# POWER_SUPPLY.net
KiCad netlist of a schematic drawn in Altium Designer
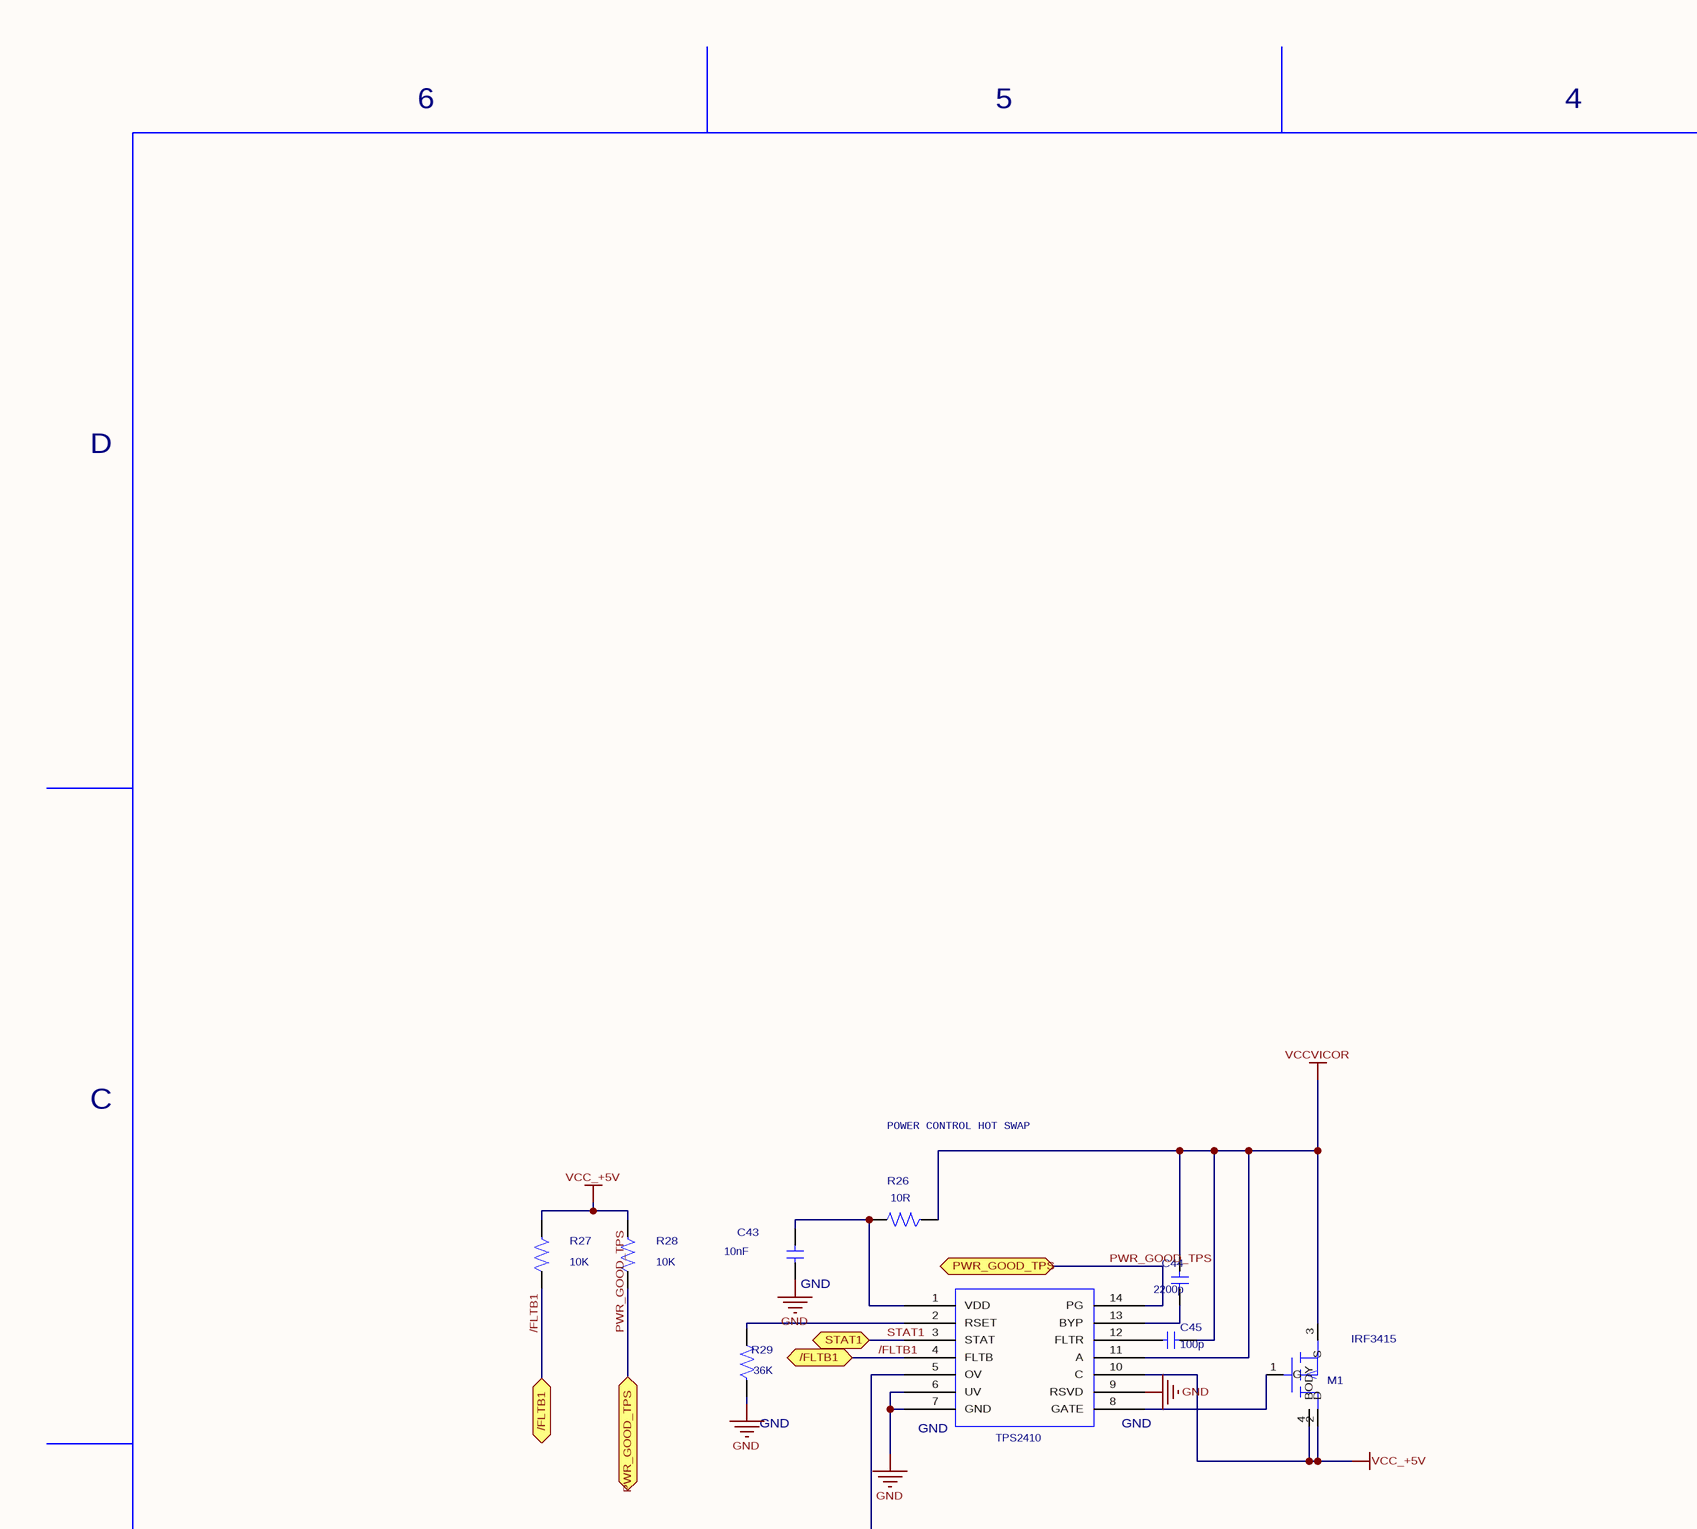
[diagram p0: POWER_SUPPLY.SchDoc, top left]
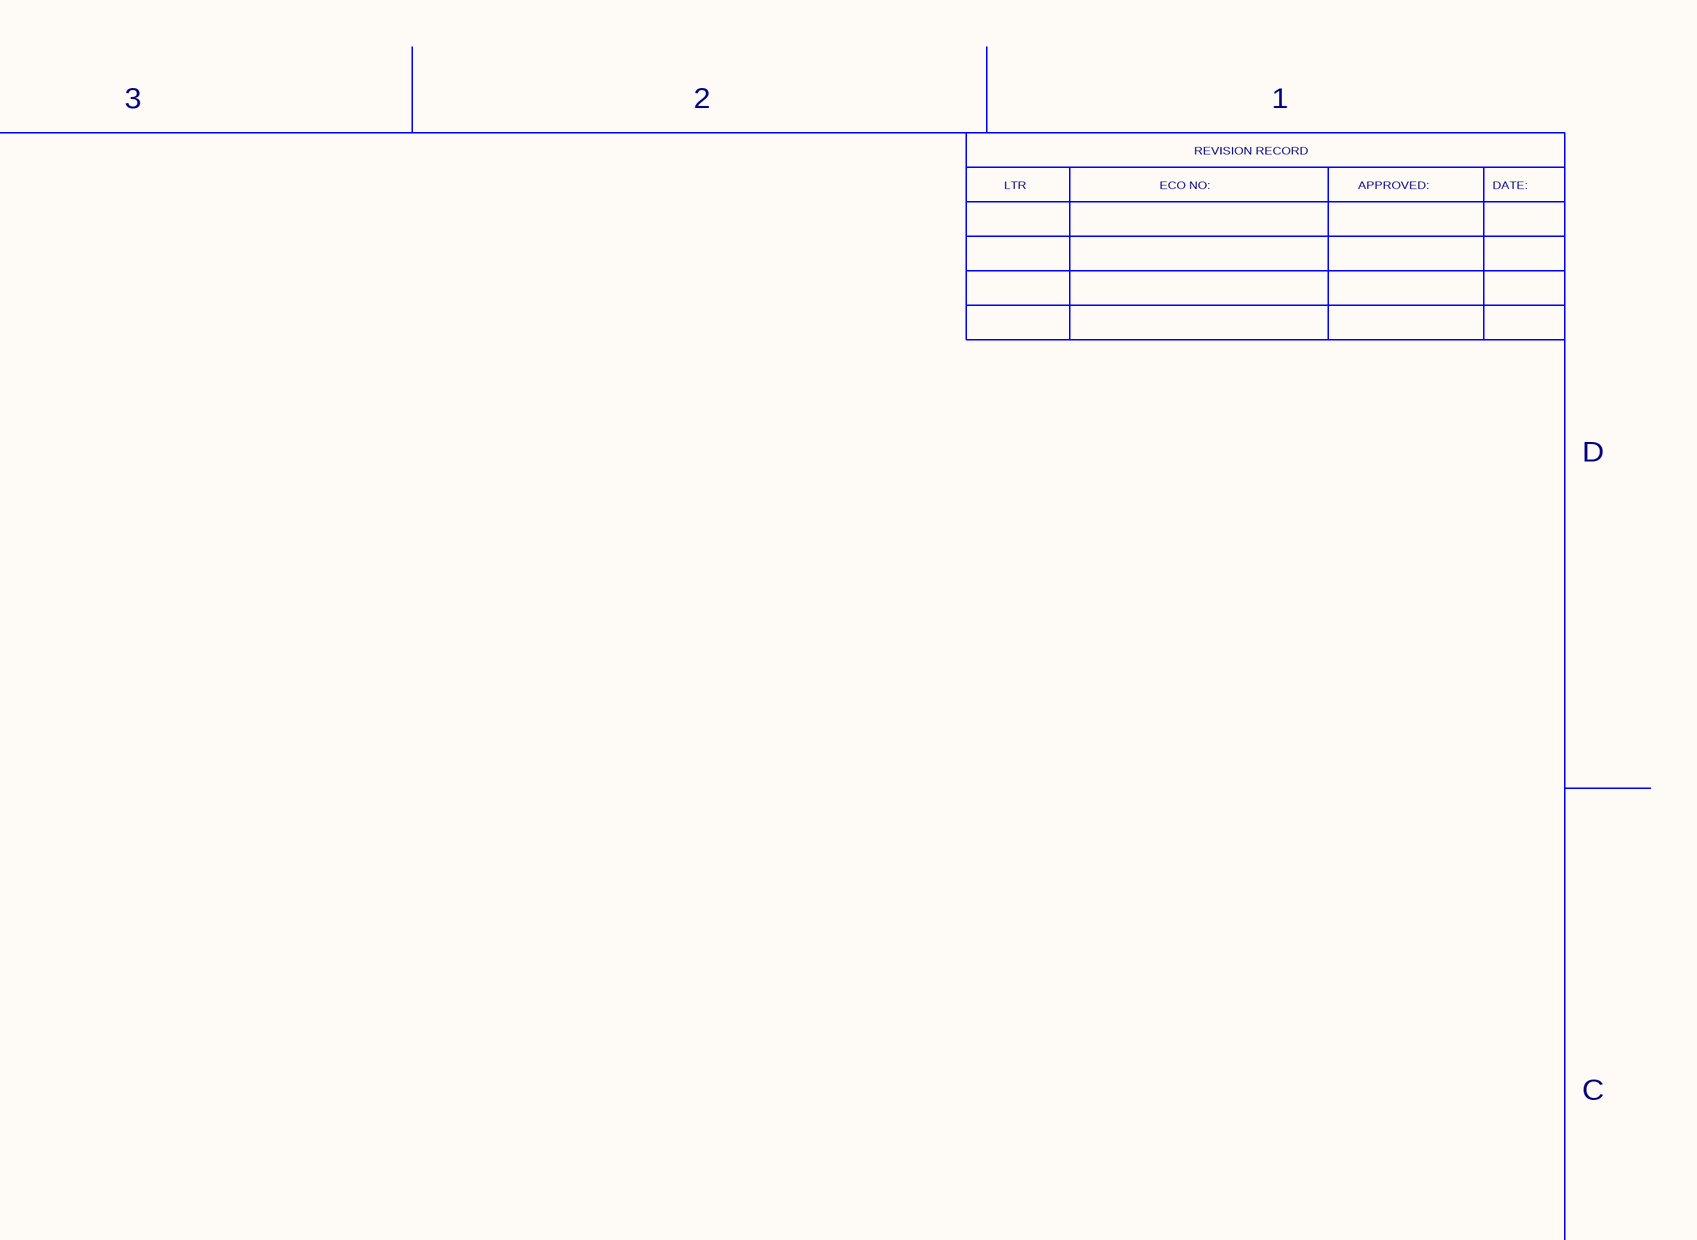
[diagram p1: POWER_SUPPLY.SchDoc, top right]
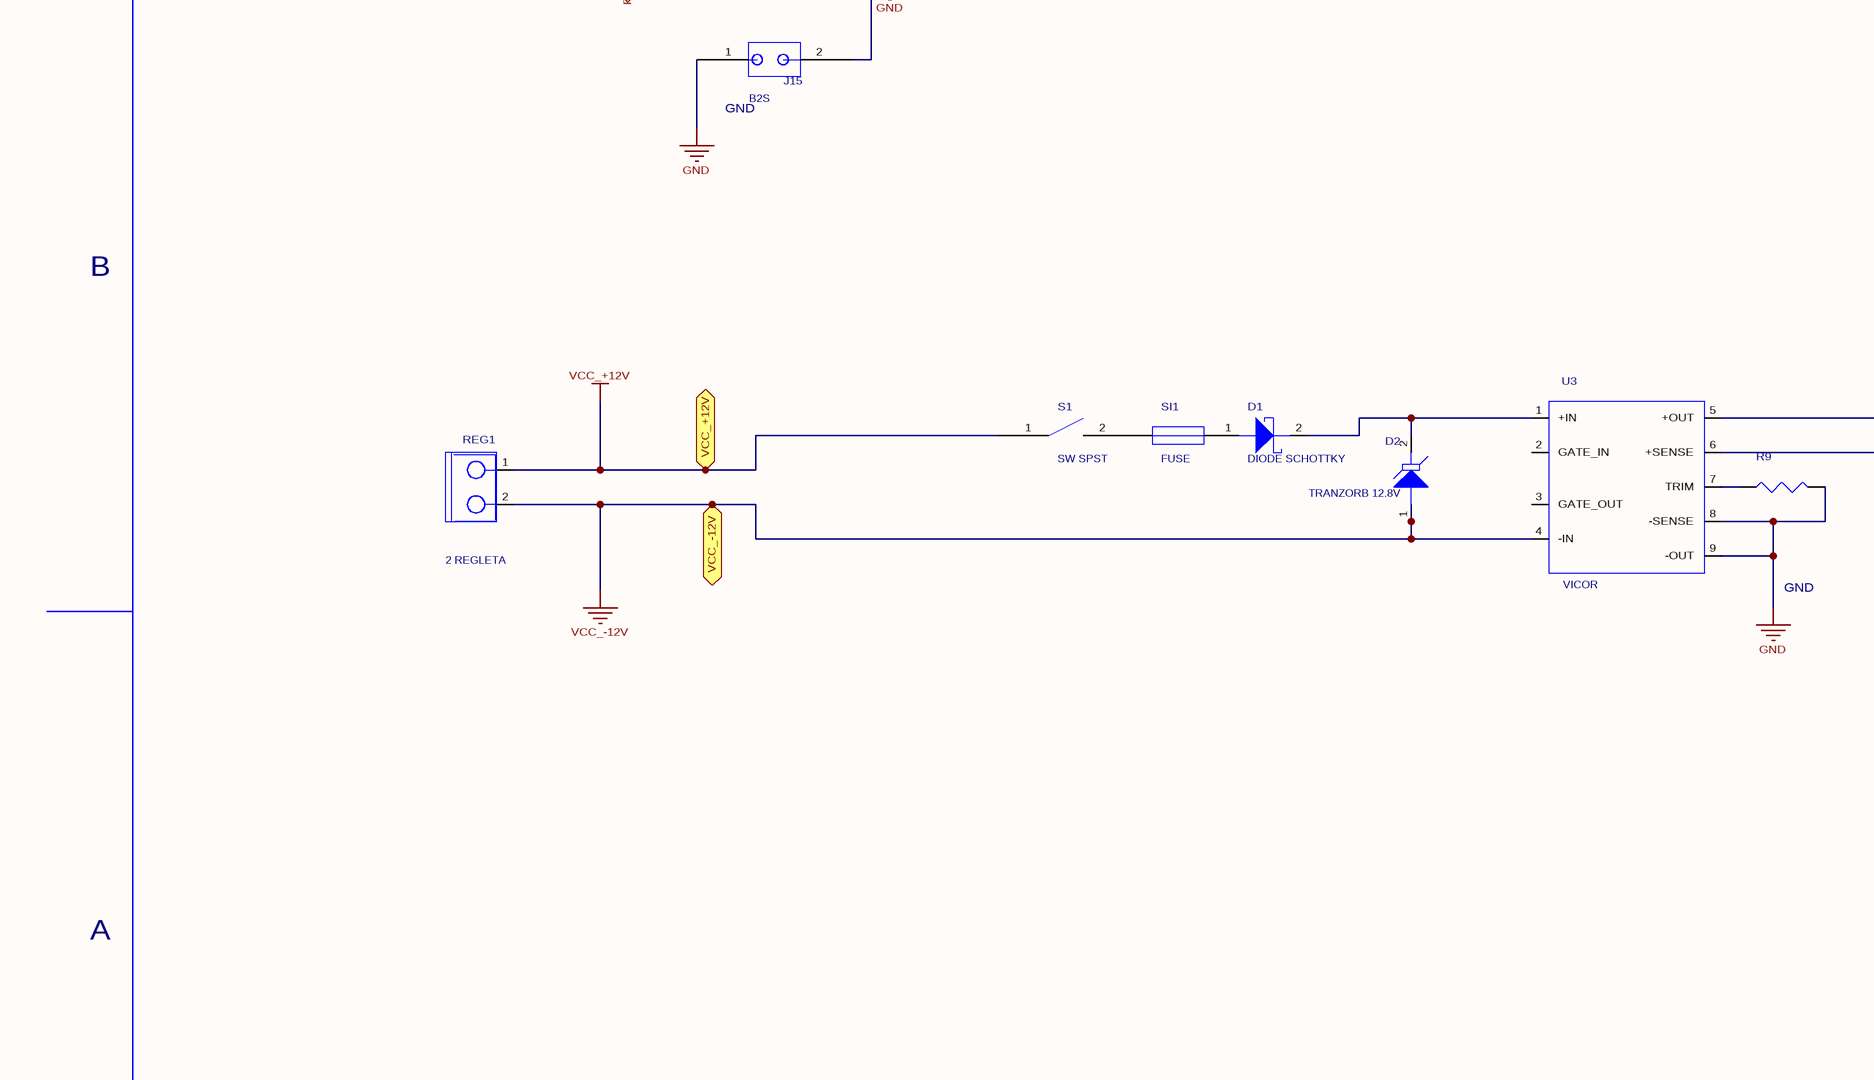
[diagram p2: POWER_SUPPLY.SchDoc, bottom left]
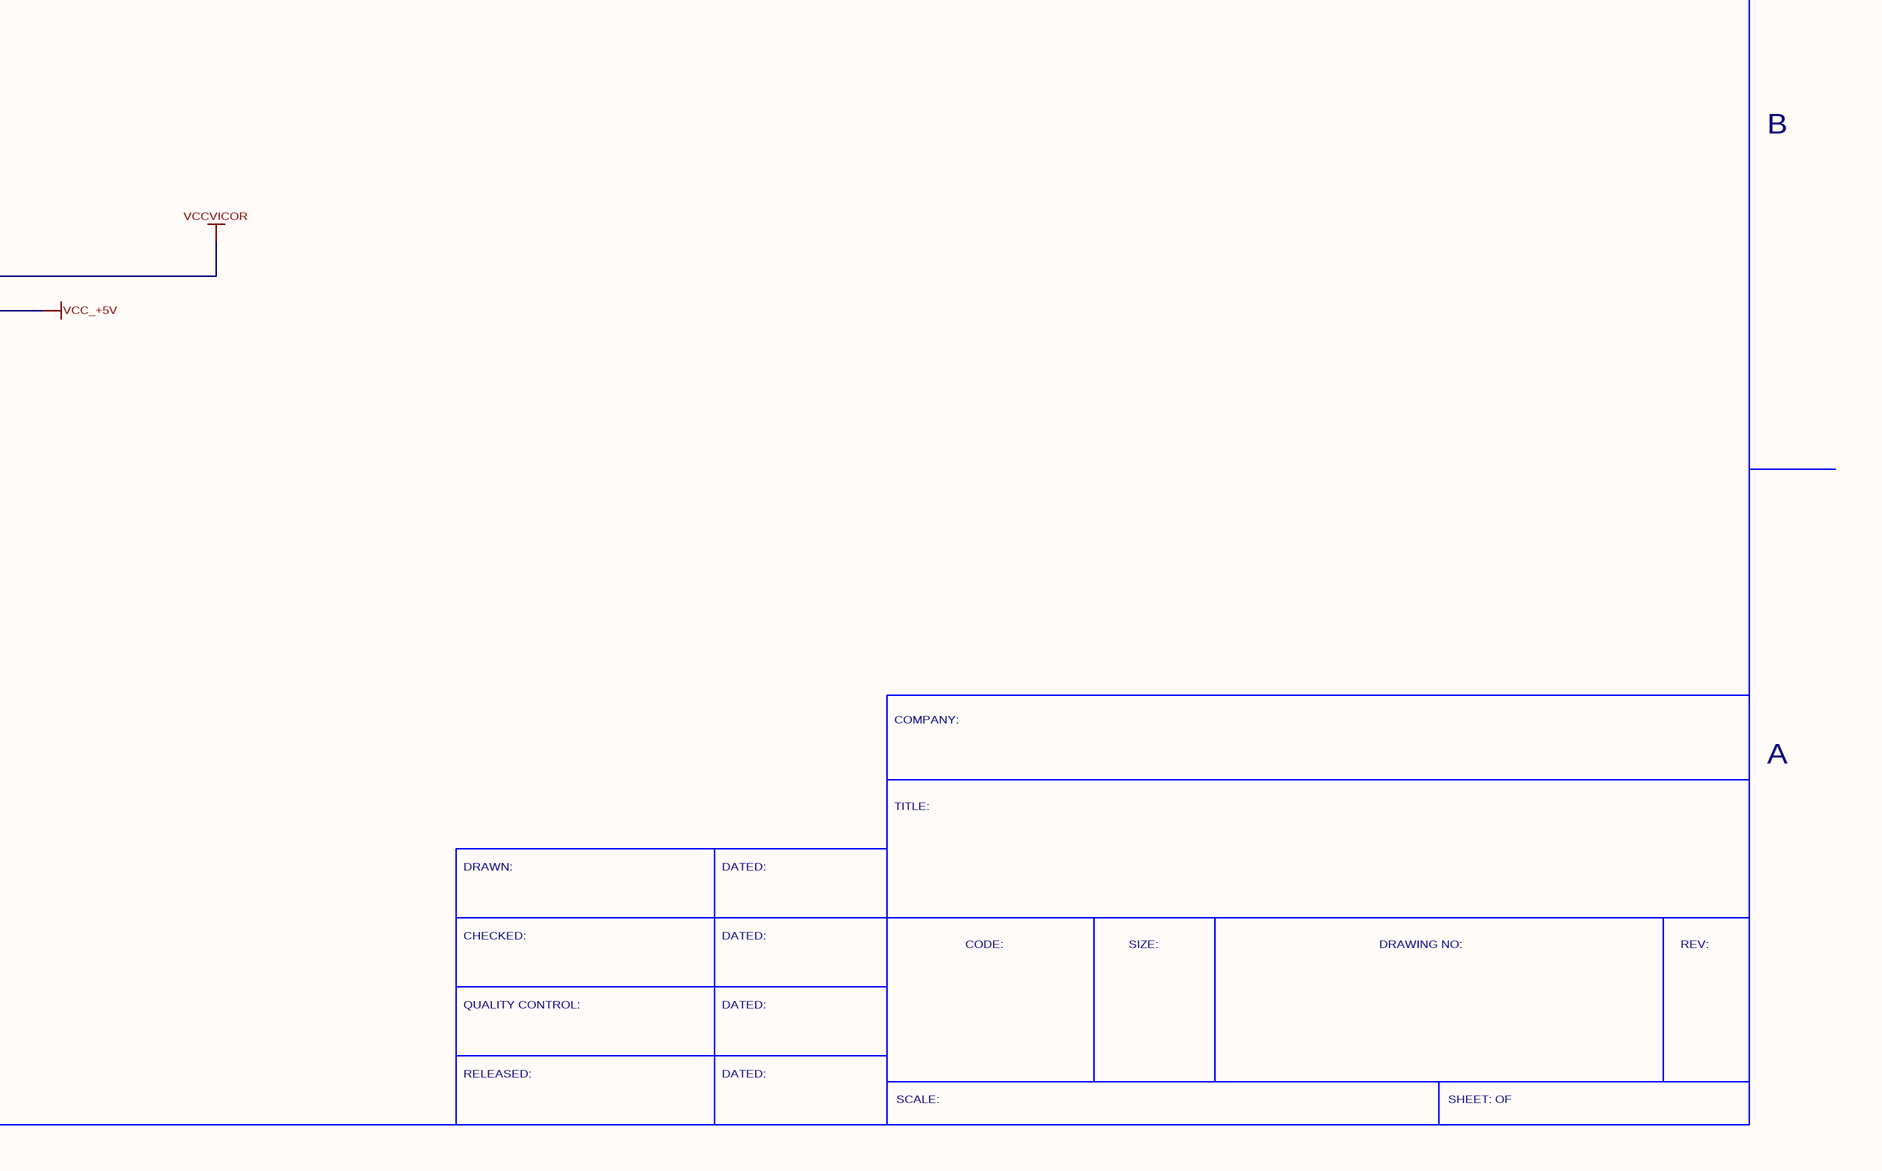
[diagram p3: POWER_SUPPLY.SchDoc, bottom right]

(export (version "E")
  (design (tool "Eeschema 10.0.6"))
  (components
    (comp (ref "C43")
      (value "10nF")
      (footprint "SM/C_0805")
      (fields (field (name "VOLTAGE") "CMAX") (field (name "Comment") "C_3"))
      (libsource (lib "*") (part "C_3"))
    )
    (comp (ref "C44")
      (value "2200p")
      (footprint "SM/C_0805")
      (fields (field (name "VOLTAGE") "CMAX") (field (name "Comment") "C_3"))
      (libsource (lib "*") (part "C_3"))
    )
    (comp (ref "C45")
      (value "100p")
      (footprint "SM/C_0805")
      (fields (field (name "VOLTAGE") "CMAX") (field (name "Comment") "C_3"))
      (libsource (lib "*") (part "C_3"))
    )
    (comp (ref "D1")
      (value "DIODE SCHOTTKY")
      (footprint "SM/DO214AB_21")
      (fields (field (name "Comment") "DIODE_SCHOTTKY_0"))
      (libsource (lib "*") (part "DIODE_SCHOTTKY_0"))
    )
    (comp (ref "D2")
      (value "TRANZORB 12.8V")
      (footprint "SM/DO214AC_21")
      (fields (field (name "Comment") "TRANZORB_0"))
      (libsource (lib "*") (part "TRANZORB_0"))
    )
    (comp (ref "J15")
      (value "B2S")
      (footprint "JUMPER_100")
      (fields (field (name "Comment") "B2S_0"))
      (libsource (lib "*") (part "B2S_0"))
    )
    (comp (ref "M1")
      (value "IRF3415")
      (footprint "IRF3415_PADS_REV1")
      (fields (field (name "Comment") "IRF3415_BODY"))
      (libsource (lib "*") (part "IRF3415_BODY"))
    )
    (comp (ref "R9") (value "RESISTOR") (footprint "SM/R_1206") (libsource (lib "*") (part "RESISTOR")))
    (comp (ref "R26")
      (value "10R")
      (footprint "SM/R_1206")
      (fields (field (name "VOLTAGE") "RVMAX") (field (name "POWER") "RMAX") (field (name "Comment") "R"))
      (libsource (lib "*") (part "R"))
    )
    (comp (ref "R27")
      (value "10K")
      (footprint "SM/R_1206")
      (fields (field (name "VOLTAGE") "RVMAX") (field (name "POWER") "RMAX") (field (name "Comment") "R"))
      (libsource (lib "*") (part "R"))
    )
    (comp (ref "R28")
      (value "10K")
      (footprint "SM/R_1206")
      (fields (field (name "VOLTAGE") "RVMAX") (field (name "POWER") "RMAX") (field (name "Comment") "R"))
      (libsource (lib "*") (part "R"))
    )
    (comp (ref "R29")
      (value "36K")
      (footprint "SM/R_1206")
      (fields (field (name "VOLTAGE") "RVMAX") (field (name "POWER") "RMAX") (field (name "Comment") "R"))
      (libsource (lib "*") (part "R"))
    )
    (comp (ref "REG1")
      (value "2 REGLETA")
      (footprint "REG2_REV8")
      (fields (field (name "Comment") "8_REGLETA_4"))
      (libsource (lib "*") (part "8_REGLETA_4"))
    )
    (comp (ref "S1")
      (value "SW SPST")
      (footprint "SW12V_REV2")
      (fields (field (name "Comment") "SW_SPST_0"))
      (libsource (lib "*") (part "SW_SPST_0"))
    )
    (comp (ref "SI1") (value "FUSE") (footprint "FUSEHOLDER3") (libsource (lib "*") (part "FUSE")))
    (comp (ref "U3") (value "VICOR") (footprint "VIKOR1") (libsource (lib "*") (part "VICOR")))
    (comp (ref "U14")
      (value "TPS2410")
      (footprint "PDSO-G14_REV7")
      (fields (field (name "Comment") "TPS2410_1"))
      (libsource (lib "*") (part "TPS2410_1"))
    )
  )
  (nets
    (net (code "1") (name "/PWR_GOOD_TPS") (class "Default")
      (node (ref "R28") (pin "2") (pinfunction "2_2") (pintype "passive"))
      (node (ref "U14") (pin "14") (pinfunction "PG_14") (pintype "open_collector"))
    )
    (net (code "2") (name "/STAT1") (class "Default")
      (node (ref "U14") (pin "3") (pinfunction "STAT_3") (pintype "passive"))
    )
    (net (code "3") (name "/{slash}FLTB1") (class "Default")
      (node (ref "R27") (pin "2") (pinfunction "2_2") (pintype "passive"))
      (node (ref "U14") (pin "4") (pinfunction "FLTB_4") (pintype "passive"))
    )
    (net (code "4") (name "GND") (class "Default")
      (node (ref "C43") (pin "1") (pinfunction "1_1") (pintype "passive"))
      (node (ref "J15") (pin "1") (pinfunction "1_1") (pintype "passive"))
      (node (ref "R29") (pin "1") (pinfunction "1_1") (pintype "passive"))
      (node (ref "R9") (pin "2") (pinfunction "2_2") (pintype "passive"))
      (node (ref "U14") (pin "6") (pinfunction "UV_6") (pintype "passive"))
      (node (ref "U14") (pin "7") (pinfunction "GND_7") (pintype "passive"))
      (node (ref "U14") (pin "9") (pinfunction "RSVD_9") (pintype "passive"))
      (node (ref "U3") (pin "8") (pinfunction "-SENSE_8") (pintype "passive"))
      (node (ref "U3") (pin "9") (pinfunction "-OUT_9") (pintype "power_in"))
    )
    (net (code "5") (name "Net-(D1-ANODE)") (class "Default")
      (node (ref "D1") (pin "1") (pinfunction "ANODE_1") (pintype "passive"))
      (node (ref "SI1") (pin "2") (pinfunction "2_2") (pintype "passive"))
    )
    (net (code "6") (name "Net-(D1-CATHODE)") (class "Default")
      (node (ref "D1") (pin "2") (pinfunction "CATHODE_2") (pintype "passive"))
      (node (ref "D2") (pin "2") (pinfunction "CATHODE_2") (pintype "passive"))
      (node (ref "U3") (pin "1") (pinfunction "+IN_1") (pintype "power_in"))
    )
    (net (code "7") (name "Net-(M1-G)") (class "Default")
      (node (ref "M1") (pin "1") (pinfunction "G_1") (pintype "passive"))
      (node (ref "U14") (pin "8") (pinfunction "GATE_8") (pintype "passive"))
    )
    (net (code "8") (name "Net-(S1-NO)") (class "Default")
      (node (ref "S1") (pin "2") (pinfunction "NO_2") (pintype "passive"))
      (node (ref "SI1") (pin "1") (pinfunction "1_1") (pintype "passive"))
    )
    (net (code "9") (name "Net-(U3-TRIM)") (class "Default")
      (node (ref "R9") (pin "1") (pinfunction "1_1") (pintype "passive"))
      (node (ref "U3") (pin "7") (pinfunction "TRIM_7") (pintype "passive"))
    )
    (net (code "10") (name "Net-(U14-BYP)") (class "Default")
      (node (ref "C44") (pin "1") (pinfunction "1_1") (pintype "passive"))
      (node (ref "U14") (pin "13") (pinfunction "BYP_13") (pintype "passive"))
    )
    (net (code "11") (name "Net-(U14-FLTR)") (class "Default")
      (node (ref "C45") (pin "2") (pinfunction "2_2") (pintype "passive"))
      (node (ref "U14") (pin "12") (pinfunction "FLTR_12") (pintype "passive"))
    )
    (net (code "12") (name "Net-(U14-OV)") (class "Default")
      (node (ref "J15") (pin "2") (pinfunction "2_2") (pintype "passive"))
      (node (ref "U14") (pin "5") (pinfunction "OV_5") (pintype "passive"))
    )
    (net (code "13") (name "Net-(U14-RSET)") (class "Default")
      (node (ref "R29") (pin "2") (pinfunction "2_2") (pintype "passive"))
      (node (ref "U14") (pin "2") (pinfunction "RSET_2") (pintype "passive"))
    )
    (net (code "14") (name "Net-(U14-VDD)") (class "Default")
      (node (ref "C43") (pin "2") (pinfunction "2_2") (pintype "passive"))
      (node (ref "R26") (pin "2") (pinfunction "2_2") (pintype "passive"))
      (node (ref "U14") (pin "1") (pinfunction "VDD_1") (pintype "passive"))
    )
    (net (code "15") (name "VCCVICOR") (class "Default")
      (node (ref "C44") (pin "2") (pinfunction "2_2") (pintype "passive"))
      (node (ref "C45") (pin "1") (pinfunction "1_1") (pintype "passive"))
      (node (ref "M1") (pin "3") (pinfunction "S_3") (pintype "passive"))
      (node (ref "R26") (pin "1") (pinfunction "1_1") (pintype "passive"))
      (node (ref "U14") (pin "11") (pinfunction "A_11") (pintype "passive"))
      (node (ref "U3") (pin "5") (pinfunction "+OUT_5") (pintype "power_in"))
    )
    (net (code "16") (name "VCC_+5V") (class "Default")
      (node (ref "M1") (pin "2") (pinfunction "D_2") (pintype "passive"))
      (node (ref "M1") (pin "4") (pinfunction "BODY_4") (pintype "passive"))
      (node (ref "R27") (pin "1") (pinfunction "1_1") (pintype "passive"))
      (node (ref "R28") (pin "1") (pinfunction "1_1") (pintype "passive"))
      (node (ref "U14") (pin "10") (pinfunction "C_10") (pintype "passive"))
      (node (ref "U3") (pin "6") (pinfunction "+SENSE_6") (pintype "passive"))
    )
    (net (code "17") (name "VCC_+12V") (class "Default")
      (node (ref "REG1") (pin "1") (pinfunction "1_1") (pintype "passive"))
      (node (ref "S1") (pin "1") (pinfunction "COMMON_1") (pintype "passive"))
    )
    (net (code "18") (name "VCC_-12V") (class "Default")
      (node (ref "D2") (pin "1") (pinfunction "ANODE_1") (pintype "passive"))
      (node (ref "REG1") (pin "2") (pinfunction "2_2") (pintype "passive"))
      (node (ref "U3") (pin "4") (pinfunction "-IN_4") (pintype "power_in"))
    )
    (net (code "19") (name "unconnected-(U3-GATE_IN-Pad2)") (class "Default")
      (node (ref "U3") (pin "2") (pinfunction "GATE_IN_2") (pintype "passive"))
    )
    (net (code "20") (name "unconnected-(U3-GATE_OUT-Pad3)") (class "Default")
      (node (ref "U3") (pin "3") (pinfunction "GATE_OUT_3") (pintype "passive"))
    )
  )
)
